# DMP_SEM_ETHERNET.net
KiCad netlist of a schematic drawn in Altium Designer
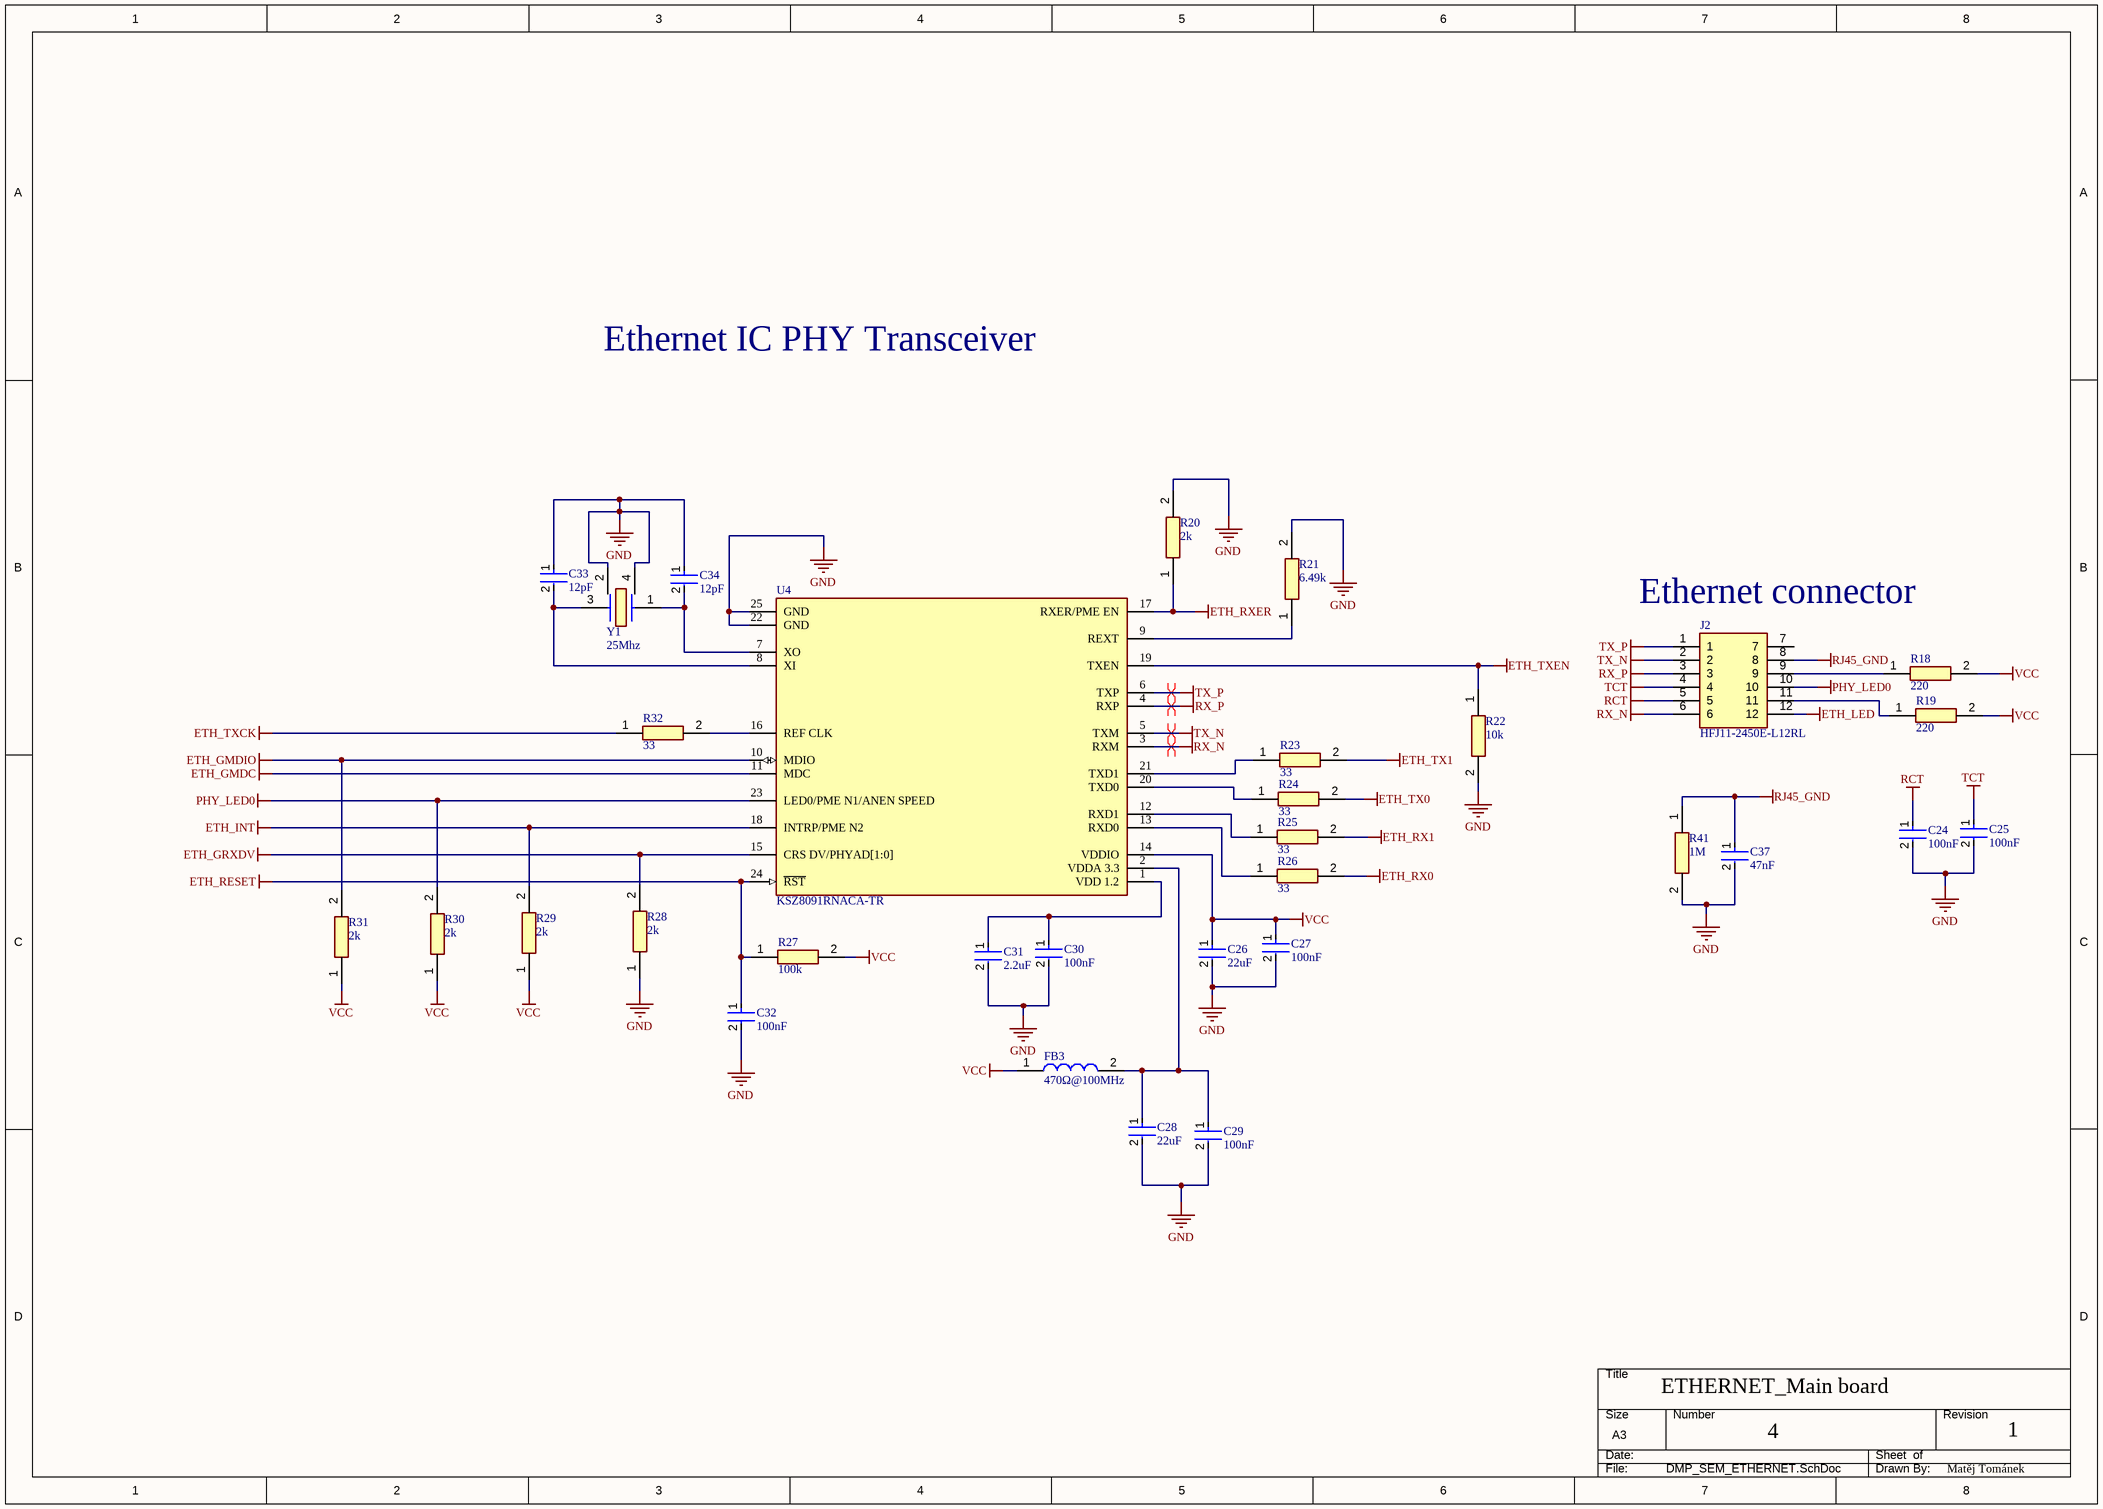
[diagram p0: DMP_SEM_ETHERNET.SchDoc]

(export (version "E")
  (design (tool "Eeschema 10.0.6"))
  (components
    (comp (ref "C24")
      (value "100nF")
      (footprint "CL05B104KO5NNNC")
      (description "Capacitor CL05B104KO5NNNC")
      (libsource (lib "DMP_Schlib_SEM_MAIN_BOARD") (part "CL05B104KO5NNNC"))
    )
    (comp (ref "C25")
      (value "100nF")
      (footprint "CL05B104KO5NNNC")
      (description "Capacitor CL05B104KO5NNNC")
      (libsource (lib "DMP_Schlib_SEM_MAIN_BOARD") (part "CL05B104KO5NNNC"))
    )
    (comp (ref "C26")
      (value "22uF")
      (footprint "GRM188R61A226ME15D")
      (description "Capacitor GRM188R61A226ME15D")
      (libsource (lib "DMP_Schlib_SEM_MAIN_BOARD") (part "GRM188R61A226ME15D"))
    )
    (comp (ref "C27")
      (value "100nF")
      (footprint "CL05B104KO5NNNC")
      (description "Capacitor CL05B104KO5NNNC")
      (libsource (lib "DMP_Schlib_SEM_MAIN_BOARD") (part "CL05B104KO5NNNC"))
    )
    (comp (ref "C28")
      (value "22uF")
      (footprint "GRM188R61A226ME15D")
      (description "Capacitor GRM188R61A226ME15D")
      (libsource (lib "DMP_Schlib_SEM_MAIN_BOARD") (part "GRM188R61A226ME15D"))
    )
    (comp (ref "C29")
      (value "100nF")
      (footprint "CL05B104KO5NNNC")
      (description "Capacitor CL05B104KO5NNNC")
      (libsource (lib "DMP_Schlib_SEM_MAIN_BOARD") (part "CL05B104KO5NNNC"))
    )
    (comp (ref "C30")
      (value "100nF")
      (footprint "CL05B104KO5NNNC")
      (description "Capacitor CL05B104KO5NNNC")
      (libsource (lib "DMP_Schlib_SEM_MAIN_BOARD") (part "CL05B104KO5NNNC"))
    )
    (comp (ref "C31")
      (value "2.2uF")
      (footprint "GRM188R61C225KAADJ")
      (description "Capacitor GRM188R61C225KAADJ")
      (libsource (lib "DMP_Schlib_SEM_MAIN_BOARD") (part "GRM188R61C225KAADJ"))
    )
    (comp (ref "C32")
      (value "100nF")
      (footprint "CL05B104KO5NNNC")
      (description "Capacitor CL05B104KO5NNNC")
      (libsource (lib "DMP_Schlib_SEM_MAIN_BOARD") (part "CL05B104KO5NNNC"))
    )
    (comp (ref "C33")
      (value "12pF")
      (footprint "C0402C120J5GACTU")
      (description "CAP CER 12PF 50V C0G/NP0 0402 C0402C120J5GACTU")
      (libsource (lib "DMP_Schlib_SEM_MAIN_BOARD") (part "C0402C120J5GACTU"))
    )
    (comp (ref "C34")
      (value "12pF")
      (footprint "C0402C120J5GACTU")
      (description "CAP CER 12PF 50V C0G/NP0 0402 C0402C120J5GACTU")
      (libsource (lib "DMP_Schlib_SEM_MAIN_BOARD") (part "C0402C120J5GACTU"))
    )
    (comp (ref "C37")
      (value "47nF")
      (footprint "C0603X473J3RAC3316")
      (description "Capacitor C0603X473J3RAC3316")
      (libsource (lib "DMP_Schlib_SEM_MAIN_BOARD") (part "C0603X473J3RAC3316"))
    )
    (comp (ref "FB3")
      (value "470Ω@100MHz")
      (footprint "BLM18PG471SN1D")
      (description "Chip Ferrite Bead, 0603, 470Ω @ 100MHz, 0.2Ω, 25%, 1A BLM18PG471SN1D")
      (libsource (lib "DMP_Schlib_SEM_MAIN_BOARD") (part "BLM18PG471SN1D"))
    )
    (comp (ref "J2")
      (value "HFJ11-2450E-L12RL")
      (footprint "HFJ11-2450E-L12RL")
      (description "RJ-45 Connector")
      (libsource (lib "DMP_Schlib_SEM_MAIN_BOARD") (part "HFJ11-2450E-L12RL"))
    )
    (comp (ref "R18")
      (value "220")
      (footprint "CRCW0603220RFKEC")
      (description "Resistor CRCW0603220RFKEC")
      (libsource (lib "DMP_Schlib_SEM_MAIN_BOARD") (part "CRCW0603220RFKEC"))
    )
    (comp (ref "R19")
      (value "220")
      (footprint "CRCW0603220RFKEC")
      (description "Resistor CRCW0603220RFKEC")
      (libsource (lib "DMP_Schlib_SEM_MAIN_BOARD") (part "CRCW0603220RFKEC"))
    )
    (comp (ref "R20")
      (value "2k")
      (footprint "ERA-2AEB202X")
      (description "Resistor")
      (libsource (lib "DMP_Schlib_SEM_MAIN_BOARD") (part "ERA-2AEB202X"))
    )
    (comp (ref "R21")
      (value "6.49k")
      (footprint "ERA-3AEB6491V")
      (description "Resistor ERA-3AEB6491V")
      (libsource (lib "DMP_Schlib_SEM_MAIN_BOARD") (part "ERA-3AEB6491V"))
    )
    (comp (ref "R22")
      (value "10k")
      (footprint "CRCW060310K0FKEA")
      (description "Resistor CRCW060310K0FKEA")
      (libsource (lib "DMP_Schlib_SEM_MAIN_BOARD") (part "CRCW060310K0FKEA"))
    )
    (comp (ref "R23")
      (value "33")
      (footprint "ERJ-U02F33R0X")
      (description "Resistor")
      (libsource (lib "DMP_Schlib_SEM_MAIN_BOARD") (part "ERJ-U02F33R0X"))
    )
    (comp (ref "R24")
      (value "33")
      (footprint "ERJ-U02F33R0X")
      (description "Resistor")
      (libsource (lib "DMP_Schlib_SEM_MAIN_BOARD") (part "ERJ-U02F33R0X"))
    )
    (comp (ref "R25")
      (value "33")
      (footprint "ERJ-U02F33R0X")
      (description "Resistor")
      (libsource (lib "DMP_Schlib_SEM_MAIN_BOARD") (part "ERJ-U02F33R0X"))
    )
    (comp (ref "R26")
      (value "33")
      (footprint "ERJ-U02F33R0X")
      (description "Resistor")
      (libsource (lib "DMP_Schlib_SEM_MAIN_BOARD") (part "ERJ-U02F33R0X"))
    )
    (comp (ref "R27")
      (value "100k")
      (footprint "ERJ-2RKF1003X")
      (description "Resistor")
      (libsource (lib "DMP_Schlib_SEM_MAIN_BOARD") (part "ERJ-2RKF1003X"))
    )
    (comp (ref "R28")
      (value "2k")
      (footprint "ERA-2AEB202X")
      (description "Resistor")
      (libsource (lib "DMP_Schlib_SEM_MAIN_BOARD") (part "ERA-2AEB202X"))
    )
    (comp (ref "R29")
      (value "2k")
      (footprint "ERA-2AEB202X")
      (description "Resistor")
      (libsource (lib "DMP_Schlib_SEM_MAIN_BOARD") (part "ERA-2AEB202X"))
    )
    (comp (ref "R30")
      (value "2k")
      (footprint "ERA-2AEB202X")
      (description "Resistor")
      (libsource (lib "DMP_Schlib_SEM_MAIN_BOARD") (part "ERA-2AEB202X"))
    )
    (comp (ref "R31")
      (value "2k")
      (footprint "ERA-2AEB202X")
      (description "Resistor")
      (libsource (lib "DMP_Schlib_SEM_MAIN_BOARD") (part "ERA-2AEB202X"))
    )
    (comp (ref "R32")
      (value "33")
      (footprint "ERJ-U02F33R0X")
      (description "Resistor")
      (libsource (lib "DMP_Schlib_SEM_MAIN_BOARD") (part "ERJ-U02F33R0X"))
    )
    (comp (ref "R41")
      (value "1M")
      (footprint "RC0402FR-071ML")
      (description "Resistor RC0402FR-071ML")
      (libsource (lib "DMP_Schlib_SEM_MAIN_BOARD") (part "RC0402FR-071ML"))
    )
    (comp (ref "U4")
      (value "KSZ8091RNACA-TR")
      (footprint "KSZ8091RNACA-TR")
      (description "IC TRANSCIEVER")
      (libsource (lib "DMP_Schlib_SEM_MAIN_BOARD") (part "KSZ8091RNACA-TR"))
    )
    (comp (ref "Y1")
      (value "25Mhz")
      (footprint "LFXTAL071758Cutt")
      (description "Crystal LFXTAL071758Cutt")
      (libsource (lib "DMP_Schlib_SEM_MAIN_BOARD") (part "LFXTAL071758Cutt"))
    )
  )
  (nets
    (net (code "1") (name "ETH_GMDC") (class "Default")
      (node (ref "U4") (pin "11") (pinfunction "MDC_11") (pintype "passive"))
    )
    (net (code "2") (name "ETH_GMDIO") (class "Default")
      (node (ref "R31") (pin "2") (pinfunction "2_2") (pintype "passive"))
      (node (ref "U4") (pin "10") (pinfunction "MDIO_10") (pintype "bidirectional"))
    )
    (net (code "3") (name "ETH_GRXDV") (class "Default")
      (node (ref "R28") (pin "2") (pinfunction "2_2") (pintype "passive"))
      (node (ref "U4") (pin "15") (pinfunction "CRS_DV/PHYAD[1:0]_15") (pintype "passive"))
    )
    (net (code "4") (name "ETH_INT") (class "Default")
      (node (ref "R29") (pin "2") (pinfunction "2_2") (pintype "passive"))
      (node (ref "U4") (pin "18") (pinfunction "INTRP/PME_N2_18") (pintype "passive"))
    )
    (net (code "5") (name "ETH_LED") (class "Default")
      (node (ref "J2") (pin "12") (pinfunction "12_12") (pintype "passive"))
    )
    (net (code "6") (name "ETH_RESET") (class "Default")
      (node (ref "C32") (pin "1") (pinfunction "1_1") (pintype "passive"))
      (node (ref "R27") (pin "1") (pinfunction "1_1") (pintype "passive"))
      (node (ref "U4") (pin "24") (pinfunction "~{RST}_24") (pintype "input"))
    )
    (net (code "7") (name "ETH_RX0") (class "Default")
      (node (ref "R26") (pin "2") (pinfunction "2_2") (pintype "passive"))
    )
    (net (code "8") (name "ETH_RX1") (class "Default")
      (node (ref "R25") (pin "2") (pinfunction "2_2") (pintype "passive"))
    )
    (net (code "9") (name "ETH_RXER") (class "Default")
      (node (ref "R20") (pin "1") (pinfunction "1_1") (pintype "passive"))
      (node (ref "U4") (pin "17") (pinfunction "RXER/PME_EN_17") (pintype "passive"))
    )
    (net (code "10") (name "ETH_TX0") (class "Default")
      (node (ref "R24") (pin "2") (pinfunction "2_2") (pintype "passive"))
    )
    (net (code "11") (name "ETH_TX1") (class "Default")
      (node (ref "R23") (pin "2") (pinfunction "2_2") (pintype "passive"))
    )
    (net (code "12") (name "ETH_TXCK") (class "Default")
      (node (ref "R32") (pin "1") (pinfunction "1_1") (pintype "passive"))
    )
    (net (code "13") (name "ETH_TXEN") (class "Default")
      (node (ref "R22") (pin "1") (pinfunction "1_1") (pintype "passive"))
      (node (ref "U4") (pin "19") (pinfunction "TXEN_19") (pintype "passive"))
    )
    (net (code "14") (name "GND") (class "Default")
      (node (ref "C24") (pin "2") (pinfunction "2_2") (pintype "passive"))
      (node (ref "C25") (pin "2") (pinfunction "2_2") (pintype "passive"))
      (node (ref "C26") (pin "2") (pinfunction "2_2") (pintype "passive"))
      (node (ref "C27") (pin "2") (pinfunction "2_2") (pintype "passive"))
      (node (ref "C28") (pin "2") (pinfunction "2_2") (pintype "passive"))
      (node (ref "C29") (pin "2") (pinfunction "2_2") (pintype "passive"))
      (node (ref "C30") (pin "2") (pinfunction "2_2") (pintype "passive"))
      (node (ref "C31") (pin "2") (pinfunction "2_2") (pintype "passive"))
      (node (ref "C32") (pin "2") (pinfunction "2_2") (pintype "passive"))
      (node (ref "C33") (pin "1") (pinfunction "1_1") (pintype "passive"))
      (node (ref "C34") (pin "1") (pinfunction "1_1") (pintype "passive"))
      (node (ref "C37") (pin "2") (pinfunction "2_2") (pintype "passive"))
      (node (ref "R20") (pin "2") (pinfunction "2_2") (pintype "passive"))
      (node (ref "R21") (pin "2") (pinfunction "2_2") (pintype "passive"))
      (node (ref "R22") (pin "2") (pinfunction "2_2") (pintype "passive"))
      (node (ref "R28") (pin "1") (pinfunction "1_1") (pintype "passive"))
      (node (ref "R41") (pin "2") (pinfunction "2_2") (pintype "passive"))
      (node (ref "U4") (pin "22") (pinfunction "GND_22") (pintype "power_in"))
      (node (ref "U4") (pin "25") (pinfunction "GND_25") (pintype "power_in"))
      (node (ref "Y1") (pin "2") (pintype "passive"))
      (node (ref "Y1") (pin "4") (pintype "passive"))
    )
    (net (code "15") (name "Net-(J2-Pad9)") (class "Default")
      (node (ref "J2") (pin "9") (pinfunction "9_9") (pintype "passive"))
      (node (ref "R18") (pin "1") (pinfunction "1_1") (pintype "passive"))
    )
    (net (code "16") (name "Net-(J2-Pad11)") (class "Default")
      (node (ref "J2") (pin "11") (pinfunction "11_11") (pintype "passive"))
      (node (ref "R19") (pin "1") (pinfunction "1_1") (pintype "passive"))
    )
    (net (code "17") (name "Net-(U4-REF_CLK)") (class "Default")
      (node (ref "R32") (pin "2") (pinfunction "2_2") (pintype "passive"))
      (node (ref "U4") (pin "16") (pinfunction "REF_CLK_16") (pintype "passive"))
    )
    (net (code "18") (name "Net-(U4-REXT)") (class "Default")
      (node (ref "R21") (pin "1") (pinfunction "1_1") (pintype "passive"))
      (node (ref "U4") (pin "9") (pinfunction "REXT_9") (pintype "passive"))
    )
    (net (code "19") (name "Net-(U4-RXD0)") (class "Default")
      (node (ref "R26") (pin "1") (pinfunction "1_1") (pintype "passive"))
      (node (ref "U4") (pin "13") (pinfunction "RXD0_13") (pintype "passive"))
    )
    (net (code "20") (name "Net-(U4-RXD1)") (class "Default")
      (node (ref "R25") (pin "1") (pinfunction "1_1") (pintype "passive"))
      (node (ref "U4") (pin "12") (pinfunction "RXD1_12") (pintype "passive"))
    )
    (net (code "21") (name "Net-(U4-TXD0)") (class "Default")
      (node (ref "R24") (pin "1") (pinfunction "1_1") (pintype "passive"))
      (node (ref "U4") (pin "20") (pinfunction "TXD0_20") (pintype "passive"))
    )
    (net (code "22") (name "Net-(U4-TXD1)") (class "Default")
      (node (ref "R23") (pin "1") (pinfunction "1_1") (pintype "passive"))
      (node (ref "U4") (pin "21") (pinfunction "TXD1_21") (pintype "passive"))
    )
    (net (code "23") (name "Net-(U4-VDDA_3.3)") (class "Default")
      (node (ref "C28") (pin "1") (pinfunction "1_1") (pintype "passive"))
      (node (ref "C29") (pin "1") (pinfunction "1_1") (pintype "passive"))
      (node (ref "FB3") (pin "2") (pinfunction "2_2") (pintype "passive"))
      (node (ref "U4") (pin "2") (pinfunction "VDDA_3.3_2") (pintype "power_in"))
    )
    (net (code "24") (name "Net-(U4-VDD_1.2)") (class "Default")
      (node (ref "C30") (pin "1") (pinfunction "1_1") (pintype "passive"))
      (node (ref "C31") (pin "1") (pinfunction "1_1") (pintype "passive"))
      (node (ref "U4") (pin "1") (pinfunction "VDD_1.2_1") (pintype "power_in"))
    )
    (net (code "25") (name "Net-(U4-XI)") (class "Default")
      (node (ref "C33") (pin "2") (pinfunction "2_2") (pintype "passive"))
      (node (ref "U4") (pin "8") (pinfunction "XI_8") (pintype "passive"))
      (node (ref "Y1") (pin "3") (pintype "passive"))
    )
    (net (code "26") (name "Net-(U4-XO)") (class "Default")
      (node (ref "C34") (pin "2") (pinfunction "2_2") (pintype "passive"))
      (node (ref "U4") (pin "7") (pinfunction "XO_7") (pintype "passive"))
      (node (ref "Y1") (pin "1") (pintype "passive"))
    )
    (net (code "27") (name "PHY_LED0") (class "Default")
      (node (ref "J2") (pin "10") (pinfunction "10_10") (pintype "passive"))
      (node (ref "R30") (pin "2") (pinfunction "2_2") (pintype "passive"))
      (node (ref "U4") (pin "23") (pinfunction "LED0/PME_N1/ANEN_SPEED_23") (pintype "passive"))
    )
    (net (code "28") (name "RCT") (class "Default")
      (node (ref "C24") (pin "1") (pinfunction "1_1") (pintype "passive"))
      (node (ref "J2") (pin "5") (pinfunction "5_5") (pintype "passive"))
    )
    (net (code "29") (name "RJ45_GND") (class "Default")
      (node (ref "C37") (pin "1") (pinfunction "1_1") (pintype "passive"))
      (node (ref "J2") (pin "8") (pinfunction "8_8") (pintype "passive"))
      (node (ref "R41") (pin "1") (pinfunction "1_1") (pintype "passive"))
    )
    (net (code "30") (name "RX_N") (class "Default")
      (node (ref "J2") (pin "6") (pinfunction "6_6") (pintype "passive"))
      (node (ref "U4") (pin "3") (pinfunction "RXM_3") (pintype "passive"))
    )
    (net (code "31") (name "RX_P") (class "Default")
      (node (ref "J2") (pin "3") (pinfunction "3_3") (pintype "passive"))
      (node (ref "U4") (pin "4") (pinfunction "RXP_4") (pintype "passive"))
    )
    (net (code "32") (name "TCT") (class "Default")
      (node (ref "C25") (pin "1") (pinfunction "1_1") (pintype "passive"))
      (node (ref "J2") (pin "4") (pinfunction "4_4") (pintype "passive"))
    )
    (net (code "33") (name "TX_N") (class "Default")
      (node (ref "J2") (pin "2") (pinfunction "2_2") (pintype "passive"))
      (node (ref "U4") (pin "5") (pinfunction "TXM_5") (pintype "passive"))
    )
    (net (code "34") (name "TX_P") (class "Default")
      (node (ref "J2") (pin "1") (pinfunction "1_1") (pintype "passive"))
      (node (ref "U4") (pin "6") (pinfunction "TXP_6") (pintype "passive"))
    )
    (net (code "35") (name "VCC") (class "Default")
      (node (ref "C26") (pin "1") (pinfunction "1_1") (pintype "passive"))
      (node (ref "C27") (pin "1") (pinfunction "1_1") (pintype "passive"))
      (node (ref "FB3") (pin "1") (pinfunction "1_1") (pintype "passive"))
      (node (ref "R18") (pin "2") (pinfunction "2_2") (pintype "passive"))
      (node (ref "R19") (pin "2") (pinfunction "2_2") (pintype "passive"))
      (node (ref "R27") (pin "2") (pinfunction "2_2") (pintype "passive"))
      (node (ref "R29") (pin "1") (pinfunction "1_1") (pintype "passive"))
      (node (ref "R30") (pin "1") (pinfunction "1_1") (pintype "passive"))
      (node (ref "R31") (pin "1") (pinfunction "1_1") (pintype "passive"))
      (node (ref "U4") (pin "14") (pinfunction "VDDIO_14") (pintype "passive"))
    )
    (net (code "36") (name "unconnected-(J2-Pad7)") (class "Default")
      (node (ref "J2") (pin "7") (pinfunction "7_7") (pintype "passive"))
    )
  )
)
